# PropGame_DevBoard_schema.net
KiCad netlist of a schematic drawn in EAGLE
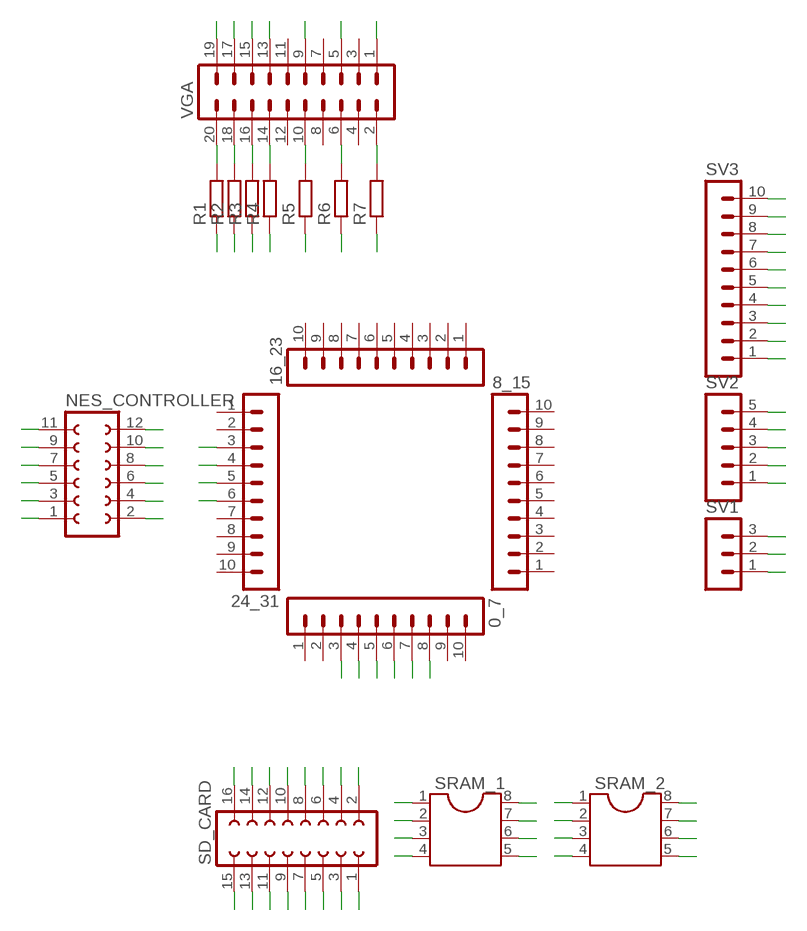
[diagram p0: schematic, sheet 1]

(export (version "E")
  (design (tool "Eeschema 10.0.6"))
  (components
    (comp (ref "0_7")
      (value "MA10-1")
      (footprint "eagle-import:MA10-1")
      (libsource (lib "eagle-import") (part "MA10-1"))
    )
    (comp (ref "8_15")
      (value "MA10-1")
      (footprint "eagle-import:MA10-1")
      (libsource (lib "eagle-import") (part "MA10-1"))
    )
    (comp (ref "16_23")
      (value "MA10-1")
      (footprint "eagle-import:MA10-1")
      (libsource (lib "eagle-import") (part "MA10-1"))
    )
    (comp (ref "24_31")
      (value "MA10-1")
      (footprint "eagle-import:MA10-1")
      (libsource (lib "eagle-import") (part "MA10-1"))
    )
    (comp (ref "NES_CONTROLLER")
      (value "FE06-2")
      (footprint "eagle-import:FE06-2")
      (libsource (lib "eagle-import") (part "FE06-2"))
    )
    (comp (ref "R1")
      (value "R-EU_0204/7")
      (footprint "eagle-import:0204_7")
      (libsource (lib "eagle-import") (part "R-EU_0204/7"))
    )
    (comp (ref "R2")
      (value "R-EU_0204/7")
      (footprint "eagle-import:0204_7")
      (libsource (lib "eagle-import") (part "R-EU_0204/7"))
    )
    (comp (ref "R3")
      (value "R-EU_0204/7")
      (footprint "eagle-import:0204_7")
      (libsource (lib "eagle-import") (part "R-EU_0204/7"))
    )
    (comp (ref "R4")
      (value "R-EU_0204/7")
      (footprint "eagle-import:0204_7")
      (libsource (lib "eagle-import") (part "R-EU_0204/7"))
    )
    (comp (ref "R5")
      (value "R-EU_0204/7")
      (footprint "eagle-import:0204_7")
      (libsource (lib "eagle-import") (part "R-EU_0204/7"))
    )
    (comp (ref "R6")
      (value "R-EU_0204/7")
      (footprint "eagle-import:0204_7")
      (libsource (lib "eagle-import") (part "R-EU_0204/7"))
    )
    (comp (ref "R7")
      (value "R-EU_0204/7")
      (footprint "eagle-import:0204_7")
      (libsource (lib "eagle-import") (part "R-EU_0204/7"))
    )
    (comp (ref "SD_CARD")
      (value "FE08-2")
      (footprint "eagle-import:FE08-2")
      (libsource (lib "eagle-import") (part "FE08-2"))
    )
    (comp (ref "SRAM_1")
      (value "DIL8")
      (footprint "eagle-import:DIL08")
      (libsource (lib "eagle-import") (part "DIL8"))
    )
    (comp (ref "SRAM_2")
      (value "DIL8")
      (footprint "eagle-import:DIL08")
      (libsource (lib "eagle-import") (part "DIL8"))
    )
    (comp (ref "SV1")
      (value "MA03-1")
      (footprint "eagle-import:MA03-1")
      (libsource (lib "eagle-import") (part "MA03-1"))
    )
    (comp (ref "SV2")
      (value "MA05-1")
      (footprint "eagle-import:MA05-1")
      (libsource (lib "eagle-import") (part "MA05-1"))
    )
    (comp (ref "SV3")
      (value "MA10-1")
      (footprint "eagle-import:MA10-1")
      (libsource (lib "eagle-import") (part "MA10-1"))
    )
    (comp (ref "VGA")
      (value "MA10-2")
      (footprint "eagle-import:MA10-2")
      (libsource (lib "eagle-import") (part "MA10-2"))
    )
  )
  (nets
    (net (code "1") (name "/3V3") (class "Default")
      (node (ref "SD_CARD") (pin "13") (pinfunction "13_13") (pintype "passive"))
      (node (ref "SD_CARD") (pin "14") (pinfunction "14_14") (pintype "passive"))
      (node (ref "SRAM_1") (pin "8") (pinfunction "8_8") (pintype "passive"))
      (node (ref "SRAM_2") (pin "8") (pinfunction "8_8") (pintype "passive"))
      (node (ref "SV1") (pin "1") (pinfunction "1_1") (pintype "passive"))
      (node (ref "SV1") (pin "2") (pinfunction "2_2") (pintype "passive"))
      (node (ref "SV1") (pin "3") (pinfunction "3_3") (pintype "passive"))
    )
    (net (code "2") (name "/5V") (class "Default")
      (node (ref "NES_CONTROLLER") (pin "3") (pinfunction "3_3") (pintype "passive"))
      (node (ref "NES_CONTROLLER") (pin "4") (pinfunction "4_4") (pintype "passive"))
      (node (ref "SD_CARD") (pin "11") (pinfunction "11_11") (pintype "passive"))
      (node (ref "SD_CARD") (pin "12") (pinfunction "12_12") (pintype "passive"))
      (node (ref "SV3") (pin "1") (pinfunction "1_1") (pintype "passive"))
      (node (ref "SV3") (pin "2") (pinfunction "2_2") (pintype "passive"))
      (node (ref "SV3") (pin "3") (pinfunction "3_3") (pintype "passive"))
    )
    (net (code "3") (name "/CLK") (class "Default")
      (node (ref "24_31") (pin "3") (pinfunction "3_3") (pintype "passive"))
      (node (ref "NES_CONTROLLER") (pin "11") (pinfunction "11_11") (pintype "passive"))
      (node (ref "NES_CONTROLLER") (pin "12") (pinfunction "12_12") (pintype "passive"))
    )
    (net (code "4") (name "/CS_1") (class "Default")
      (node (ref "0_7") (pin "6") (pinfunction "6_6") (pintype "passive"))
      (node (ref "SD_CARD") (pin "10") (pinfunction "10_10") (pintype "passive"))
      (node (ref "SD_CARD") (pin "9") (pinfunction "9_9") (pintype "passive"))
    )
    (net (code "5") (name "/CS_2") (class "Default")
      (node (ref "0_7") (pin "7") (pinfunction "7_7") (pintype "passive"))
      (node (ref "SRAM_1") (pin "1") (pinfunction "1_1") (pintype "passive"))
    )
    (net (code "6") (name "/CS_3") (class "Default")
      (node (ref "0_7") (pin "8") (pinfunction "8_8") (pintype "passive"))
      (node (ref "SRAM_2") (pin "1") (pinfunction "1_1") (pintype "passive"))
    )
    (net (code "7") (name "/DATA1") (class "Default")
      (node (ref "24_31") (pin "5") (pinfunction "5_5") (pintype "passive"))
      (node (ref "NES_CONTROLLER") (pin "7") (pinfunction "7_7") (pintype "passive"))
      (node (ref "NES_CONTROLLER") (pin "8") (pinfunction "8_8") (pintype "passive"))
    )
    (net (code "8") (name "/DATA2") (class "Default")
      (node (ref "24_31") (pin "6") (pinfunction "6_6") (pintype "passive"))
      (node (ref "NES_CONTROLLER") (pin "5") (pinfunction "5_5") (pintype "passive"))
      (node (ref "NES_CONTROLLER") (pin "6") (pinfunction "6_6") (pintype "passive"))
    )
    (net (code "9") (name "/GND") (class "Default")
      (node (ref "NES_CONTROLLER") (pin "1") (pinfunction "1_1") (pintype "passive"))
      (node (ref "NES_CONTROLLER") (pin "2") (pinfunction "2_2") (pintype "passive"))
      (node (ref "SD_CARD") (pin "1") (pinfunction "1_1") (pintype "passive"))
      (node (ref "SD_CARD") (pin "15") (pinfunction "15_15") (pintype "passive"))
      (node (ref "SD_CARD") (pin "16") (pinfunction "16_16") (pintype "passive"))
      (node (ref "SD_CARD") (pin "2") (pinfunction "2_2") (pintype "passive"))
      (node (ref "SRAM_1") (pin "4") (pinfunction "4_4") (pintype "passive"))
      (node (ref "SRAM_2") (pin "4") (pinfunction "4_4") (pintype "passive"))
      (node (ref "SV2") (pin "1") (pinfunction "1_1") (pintype "passive"))
      (node (ref "SV2") (pin "2") (pinfunction "2_2") (pintype "passive"))
      (node (ref "SV2") (pin "3") (pinfunction "3_3") (pintype "passive"))
      (node (ref "SV2") (pin "4") (pinfunction "4_4") (pintype "passive"))
      (node (ref "SV2") (pin "5") (pinfunction "5_5") (pintype "passive"))
      (node (ref "SV3") (pin "10") (pinfunction "10_10") (pintype "passive"))
      (node (ref "SV3") (pin "4") (pinfunction "4_4") (pintype "passive"))
      (node (ref "SV3") (pin "5") (pinfunction "5_5") (pintype "passive"))
      (node (ref "SV3") (pin "6") (pinfunction "6_6") (pintype "passive"))
      (node (ref "SV3") (pin "7") (pinfunction "7_7") (pintype "passive"))
      (node (ref "SV3") (pin "8") (pinfunction "8_8") (pintype "passive"))
      (node (ref "SV3") (pin "9") (pinfunction "9_9") (pintype "passive"))
    )
    (net (code "10") (name "/LATCH") (class "Default")
      (node (ref "24_31") (pin "4") (pinfunction "4_4") (pintype "passive"))
      (node (ref "NES_CONTROLLER") (pin "10") (pinfunction "10_10") (pintype "passive"))
      (node (ref "NES_CONTROLLER") (pin "9") (pinfunction "9_9") (pintype "passive"))
    )
    (net (code "11") (name "/MISO") (class "Default")
      (node (ref "0_7") (pin "5") (pinfunction "5_5") (pintype "passive"))
      (node (ref "SD_CARD") (pin "3") (pinfunction "3_3") (pintype "passive"))
      (node (ref "SD_CARD") (pin "4") (pinfunction "4_4") (pintype "passive"))
      (node (ref "SRAM_1") (pin "2") (pinfunction "2_2") (pintype "passive"))
      (node (ref "SRAM_2") (pin "2") (pinfunction "2_2") (pintype "passive"))
    )
    (net (code "12") (name "/MOSI") (class "Default")
      (node (ref "0_7") (pin "4") (pinfunction "4_4") (pintype "passive"))
      (node (ref "SD_CARD") (pin "7") (pinfunction "7_7") (pintype "passive"))
      (node (ref "SD_CARD") (pin "8") (pinfunction "8_8") (pintype "passive"))
      (node (ref "SRAM_1") (pin "5") (pinfunction "5_5") (pintype "passive"))
      (node (ref "SRAM_2") (pin "5") (pinfunction "5_5") (pintype "passive"))
    )
    (net (code "13") (name "/SCK") (class "Default")
      (node (ref "0_7") (pin "3") (pinfunction "3_3") (pintype "passive"))
      (node (ref "SD_CARD") (pin "5") (pinfunction "5_5") (pintype "passive"))
      (node (ref "SD_CARD") (pin "6") (pinfunction "6_6") (pintype "passive"))
      (node (ref "SRAM_1") (pin "6") (pinfunction "6_6") (pintype "passive"))
      (node (ref "SRAM_2") (pin "6") (pinfunction "6_6") (pintype "passive"))
    )
    (net (code "14") (name "/W_1") (class "Default")
      (node (ref "R1") (pin "1") (pinfunction "1_1") (pintype "passive"))
      (node (ref "VGA") (pin "19") (pinfunction "19_19") (pintype "passive"))
    )
    (net (code "15") (name "/W_2") (class "Default")
      (node (ref "R2") (pin "1") (pinfunction "1_1") (pintype "passive"))
      (node (ref "VGA") (pin "17") (pinfunction "17_17") (pintype "passive"))
    )
    (net (code "16") (name "/W_3") (class "Default")
      (node (ref "R3") (pin "1") (pinfunction "1_1") (pintype "passive"))
      (node (ref "VGA") (pin "15") (pinfunction "15_15") (pintype "passive"))
    )
    (net (code "17") (name "/W_4") (class "Default")
      (node (ref "R4") (pin "1") (pinfunction "1_1") (pintype "passive"))
      (node (ref "VGA") (pin "13") (pinfunction "13_13") (pintype "passive"))
    )
    (net (code "18") (name "/W_5") (class "Default")
      (node (ref "R5") (pin "1") (pinfunction "1_1") (pintype "passive"))
      (node (ref "VGA") (pin "9") (pinfunction "9_9") (pintype "passive"))
    )
    (net (code "19") (name "/W_6") (class "Default")
      (node (ref "R6") (pin "1") (pinfunction "1_1") (pintype "passive"))
      (node (ref "VGA") (pin "5") (pinfunction "5_5") (pintype "passive"))
    )
    (net (code "20") (name "/W_7") (class "Default")
      (node (ref "R7") (pin "1") (pinfunction "1_1") (pintype "passive"))
      (node (ref "VGA") (pin "1") (pinfunction "1_1") (pintype "passive"))
    )
    (net (code "21") (name "Net-(R1-Pad2)") (class "Default")
      (node (ref "R1") (pin "2") (pinfunction "2_2") (pintype "passive"))
      (node (ref "VGA") (pin "20") (pinfunction "20_20") (pintype "passive"))
    )
    (net (code "22") (name "Net-(R2-Pad2)") (class "Default")
      (node (ref "R2") (pin "2") (pinfunction "2_2") (pintype "passive"))
      (node (ref "VGA") (pin "18") (pinfunction "18_18") (pintype "passive"))
    )
    (net (code "23") (name "Net-(R3-Pad2)") (class "Default")
      (node (ref "R3") (pin "2") (pinfunction "2_2") (pintype "passive"))
      (node (ref "VGA") (pin "16") (pinfunction "16_16") (pintype "passive"))
    )
    (net (code "24") (name "Net-(R4-Pad2)") (class "Default")
      (node (ref "R4") (pin "2") (pinfunction "2_2") (pintype "passive"))
      (node (ref "VGA") (pin "14") (pinfunction "14_14") (pintype "passive"))
    )
    (net (code "25") (name "Net-(R5-Pad2)") (class "Default")
      (node (ref "R5") (pin "2") (pinfunction "2_2") (pintype "passive"))
      (node (ref "VGA") (pin "10") (pinfunction "10_10") (pintype "passive"))
    )
    (net (code "26") (name "Net-(R6-Pad2)") (class "Default")
      (node (ref "R6") (pin "2") (pinfunction "2_2") (pintype "passive"))
      (node (ref "VGA") (pin "6") (pinfunction "6_6") (pintype "passive"))
    )
    (net (code "27") (name "Net-(R7-Pad2)") (class "Default")
      (node (ref "R7") (pin "2") (pinfunction "2_2") (pintype "passive"))
      (node (ref "VGA") (pin "2") (pinfunction "2_2") (pintype "passive"))
    )
    (net (code "28") (name "unconnected-(0_7-Pad1)") (class "Default")
      (node (ref "0_7") (pin "1") (pinfunction "1_1") (pintype "passive"))
    )
    (net (code "29") (name "unconnected-(0_7-Pad2)") (class "Default")
      (node (ref "0_7") (pin "2") (pinfunction "2_2") (pintype "passive"))
    )
    (net (code "30") (name "unconnected-(0_7-Pad9)") (class "Default")
      (node (ref "0_7") (pin "9") (pinfunction "9_9") (pintype "passive"))
    )
    (net (code "31") (name "unconnected-(0_7-Pad10)") (class "Default")
      (node (ref "0_7") (pin "10") (pinfunction "10_10") (pintype "passive"))
    )
    (net (code "32") (name "unconnected-(8_15-Pad1)") (class "Default")
      (node (ref "8_15") (pin "1") (pinfunction "1_1") (pintype "passive"))
    )
    (net (code "33") (name "unconnected-(8_15-Pad2)") (class "Default")
      (node (ref "8_15") (pin "2") (pinfunction "2_2") (pintype "passive"))
    )
    (net (code "34") (name "unconnected-(8_15-Pad3)") (class "Default")
      (node (ref "8_15") (pin "3") (pinfunction "3_3") (pintype "passive"))
    )
    (net (code "35") (name "unconnected-(8_15-Pad4)") (class "Default")
      (node (ref "8_15") (pin "4") (pinfunction "4_4") (pintype "passive"))
    )
    (net (code "36") (name "unconnected-(8_15-Pad5)") (class "Default")
      (node (ref "8_15") (pin "5") (pinfunction "5_5") (pintype "passive"))
    )
    (net (code "37") (name "unconnected-(8_15-Pad6)") (class "Default")
      (node (ref "8_15") (pin "6") (pinfunction "6_6") (pintype "passive"))
    )
    (net (code "38") (name "unconnected-(8_15-Pad7)") (class "Default")
      (node (ref "8_15") (pin "7") (pinfunction "7_7") (pintype "passive"))
    )
    (net (code "39") (name "unconnected-(8_15-Pad8)") (class "Default")
      (node (ref "8_15") (pin "8") (pinfunction "8_8") (pintype "passive"))
    )
    (net (code "40") (name "unconnected-(8_15-Pad9)") (class "Default")
      (node (ref "8_15") (pin "9") (pinfunction "9_9") (pintype "passive"))
    )
    (net (code "41") (name "unconnected-(8_15-Pad10)") (class "Default")
      (node (ref "8_15") (pin "10") (pinfunction "10_10") (pintype "passive"))
    )
    (net (code "42") (name "unconnected-(16_23-Pad1)") (class "Default")
      (node (ref "16_23") (pin "1") (pinfunction "1_1") (pintype "passive"))
    )
    (net (code "43") (name "unconnected-(16_23-Pad2)") (class "Default")
      (node (ref "16_23") (pin "2") (pinfunction "2_2") (pintype "passive"))
    )
    (net (code "44") (name "unconnected-(16_23-Pad3)") (class "Default")
      (node (ref "16_23") (pin "3") (pinfunction "3_3") (pintype "passive"))
    )
    (net (code "45") (name "unconnected-(16_23-Pad4)") (class "Default")
      (node (ref "16_23") (pin "4") (pinfunction "4_4") (pintype "passive"))
    )
    (net (code "46") (name "unconnected-(16_23-Pad5)") (class "Default")
      (node (ref "16_23") (pin "5") (pinfunction "5_5") (pintype "passive"))
    )
    (net (code "47") (name "unconnected-(16_23-Pad6)") (class "Default")
      (node (ref "16_23") (pin "6") (pinfunction "6_6") (pintype "passive"))
    )
    (net (code "48") (name "unconnected-(16_23-Pad7)") (class "Default")
      (node (ref "16_23") (pin "7") (pinfunction "7_7") (pintype "passive"))
    )
    (net (code "49") (name "unconnected-(16_23-Pad8)") (class "Default")
      (node (ref "16_23") (pin "8") (pinfunction "8_8") (pintype "passive"))
    )
    (net (code "50") (name "unconnected-(16_23-Pad9)") (class "Default")
      (node (ref "16_23") (pin "9") (pinfunction "9_9") (pintype "passive"))
    )
    (net (code "51") (name "unconnected-(16_23-Pad10)") (class "Default")
      (node (ref "16_23") (pin "10") (pinfunction "10_10") (pintype "passive"))
    )
    (net (code "52") (name "unconnected-(24_31-Pad1)") (class "Default")
      (node (ref "24_31") (pin "1") (pinfunction "1_1") (pintype "passive"))
    )
    (net (code "53") (name "unconnected-(24_31-Pad2)") (class "Default")
      (node (ref "24_31") (pin "2") (pinfunction "2_2") (pintype "passive"))
    )
    (net (code "54") (name "unconnected-(24_31-Pad7)") (class "Default")
      (node (ref "24_31") (pin "7") (pinfunction "7_7") (pintype "passive"))
    )
    (net (code "55") (name "unconnected-(24_31-Pad8)") (class "Default")
      (node (ref "24_31") (pin "8") (pinfunction "8_8") (pintype "passive"))
    )
    (net (code "56") (name "unconnected-(24_31-Pad9)") (class "Default")
      (node (ref "24_31") (pin "9") (pinfunction "9_9") (pintype "passive"))
    )
    (net (code "57") (name "unconnected-(24_31-Pad10)") (class "Default")
      (node (ref "24_31") (pin "10") (pinfunction "10_10") (pintype "passive"))
    )
    (net (code "58") (name "unconnected-(SRAM_1-Pad3)") (class "Default")
      (node (ref "SRAM_1") (pin "3") (pinfunction "3_3") (pintype "passive"))
    )
    (net (code "59") (name "unconnected-(SRAM_1-Pad7)") (class "Default")
      (node (ref "SRAM_1") (pin "7") (pinfunction "7_7") (pintype "passive"))
    )
    (net (code "60") (name "unconnected-(SRAM_2-Pad3)") (class "Default")
      (node (ref "SRAM_2") (pin "3") (pinfunction "3_3") (pintype "passive"))
    )
    (net (code "61") (name "unconnected-(SRAM_2-Pad7)") (class "Default")
      (node (ref "SRAM_2") (pin "7") (pinfunction "7_7") (pintype "passive"))
    )
    (net (code "62") (name "unconnected-(VGA-Pad3)") (class "Default")
      (node (ref "VGA") (pin "3") (pinfunction "3_3") (pintype "passive"))
    )
    (net (code "63") (name "unconnected-(VGA-Pad4)") (class "Default")
      (node (ref "VGA") (pin "4") (pinfunction "4_4") (pintype "passive"))
    )
    (net (code "64") (name "unconnected-(VGA-Pad7)") (class "Default")
      (node (ref "VGA") (pin "7") (pinfunction "7_7") (pintype "passive"))
    )
    (net (code "65") (name "unconnected-(VGA-Pad8)") (class "Default")
      (node (ref "VGA") (pin "8") (pinfunction "8_8") (pintype "passive"))
    )
    (net (code "66") (name "unconnected-(VGA-Pad11)") (class "Default")
      (node (ref "VGA") (pin "11") (pinfunction "11_11") (pintype "passive"))
    )
    (net (code "67") (name "unconnected-(VGA-Pad12)") (class "Default")
      (node (ref "VGA") (pin "12") (pinfunction "12_12") (pintype "passive"))
    )
  )
)
